# EPU.net
KiCad netlist of a schematic drawn in Altium Designer
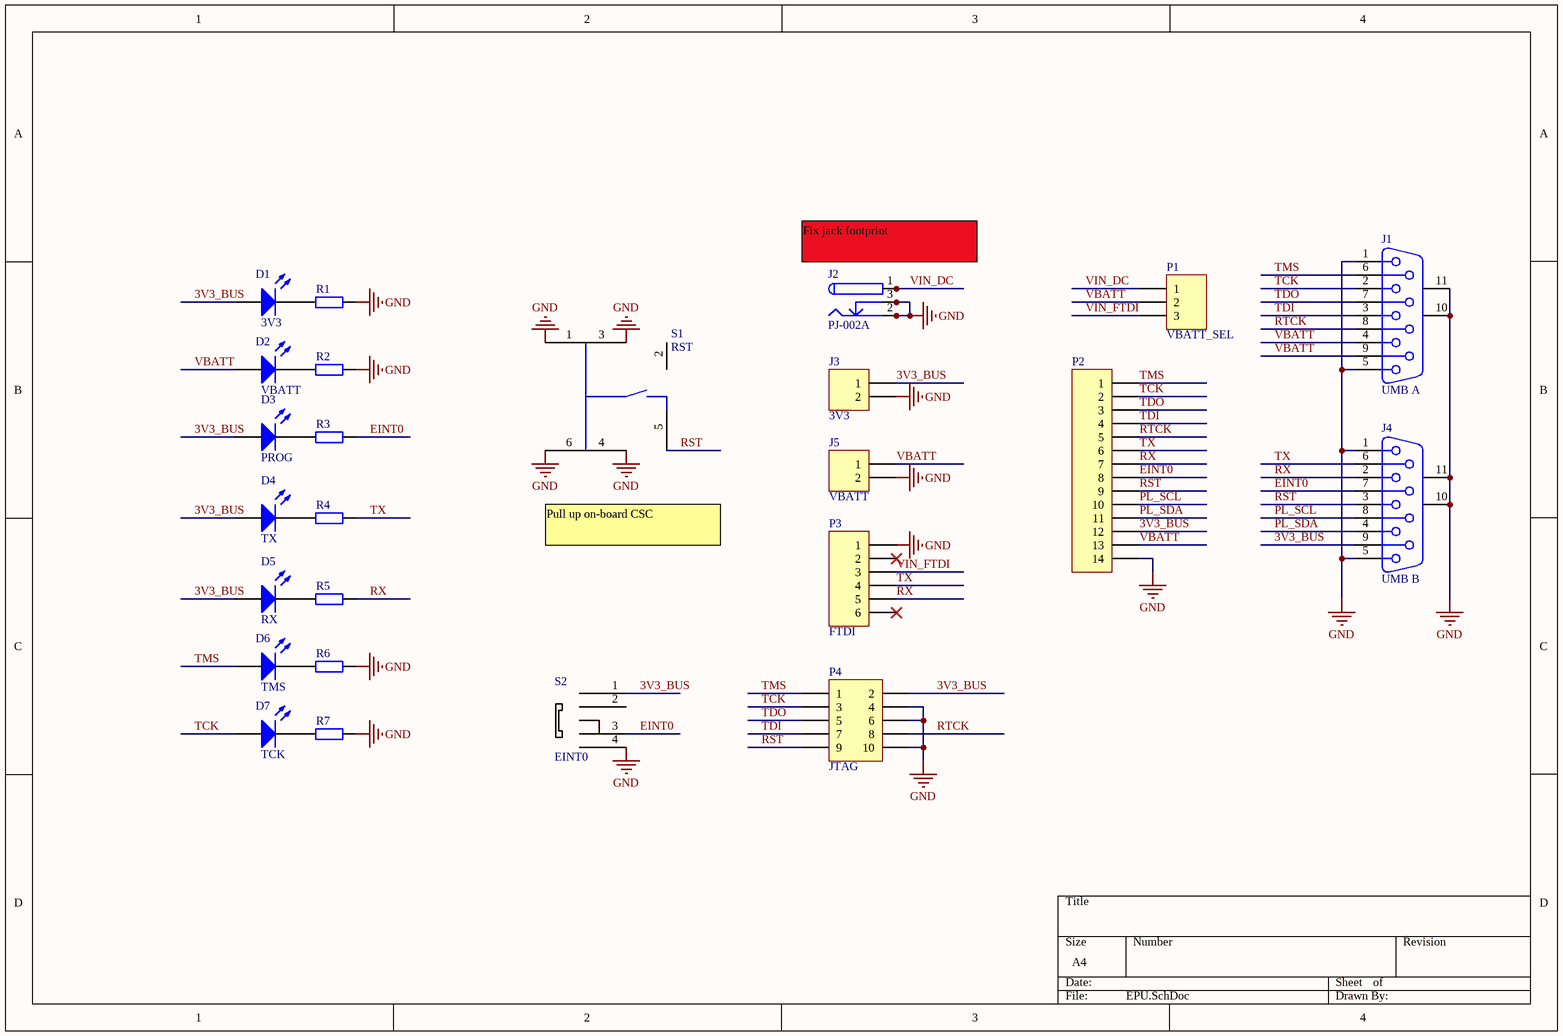
[diagram p0: EPU.SchDoc]

(export (version "E")
  (design (tool "Eeschema 10.0.6"))
  (components
    (comp (ref "D1")
      (value "3V3")
      (footprint "ASMT-Rx45")
      (description "Typical INFRARED GaAs LED 0603")
      (fields (field (name "PUBLISHER") "Altium Limited"))
      (libsource (lib "CSC") (part "LED"))
    )
    (comp (ref "D2")
      (value "VBATT")
      (footprint "ASMT-Rx45")
      (description "Typical INFRARED GaAs LED 0603")
      (fields (field (name "PUBLISHER") "Altium Limited"))
      (libsource (lib "CSC") (part "LED"))
    )
    (comp (ref "D3")
      (value "PROG")
      (footprint "ASMT-Rx45")
      (description "Typical INFRARED GaAs LED 0603")
      (fields (field (name "PUBLISHER") "Altium Limited"))
      (libsource (lib "CSC") (part "LED"))
    )
    (comp (ref "D4")
      (value "TX")
      (footprint "ASMT-Rx45")
      (description "Typical INFRARED GaAs LED 0603")
      (fields (field (name "PUBLISHER") "Altium Limited"))
      (libsource (lib "CSC") (part "LED"))
    )
    (comp (ref "D5")
      (value "RX")
      (footprint "ASMT-Rx45")
      (description "Typical INFRARED GaAs LED 0603")
      (fields (field (name "PUBLISHER") "Altium Limited"))
      (libsource (lib "CSC") (part "LED"))
    )
    (comp (ref "D6")
      (value "TMS")
      (footprint "ASMT-Rx45")
      (description "Typical INFRARED GaAs LED 0603")
      (fields (field (name "PUBLISHER") "Altium Limited"))
      (libsource (lib "CSC") (part "LED"))
    )
    (comp (ref "D7")
      (value "TCK")
      (footprint "ASMT-Rx45")
      (description "Typical INFRARED GaAs LED 0603")
      (fields (field (name "PUBLISHER") "Altium Limited"))
      (libsource (lib "CSC") (part "LED"))
    )
    (comp (ref "J1")
      (value "UMB A")
      (footprint "DSUB1.385-2H9")
      (description "Receptacle Assembly, 9 Position, Right Angle")
      (fields (field (name "PUBLISHER") "Altium Limited"))
      (libsource (lib "Miscellaneous Connectors") (part "D Connector 9"))
    )
    (comp (ref "J2")
      (value "PJ-002A")
      (footprint "PJ-002A")
      (description "Low Voltage Power Supply Connector")
      (fields (field (name "PUBLISHER") "Altium Limited"))
      (libsource (lib "Miscellaneous Connectors") (part "PWR2.5"))
    )
    (comp (ref "J3")
      (value "3V3")
      (footprint "5.05mm Terminal Block")
      (description "Header, 2-Pin")
      (fields (field (name "PUBLISHER") "Altium Limited"))
      (libsource (lib "Miscellaneous Connectors") (part "Header 2"))
    )
    (comp (ref "J4")
      (value "UMB B")
      (footprint "DSUB1.385-2H9")
      (description "Receptacle Assembly, 9 Position, Right Angle")
      (fields (field (name "PUBLISHER") "Altium Limited"))
      (libsource (lib "Miscellaneous Connectors") (part "D Connector 9"))
    )
    (comp (ref "J5")
      (value "VBATT")
      (footprint "5.05mm Terminal Block")
      (description "Header, 2-Pin")
      (fields (field (name "PUBLISHER") "Altium Limited"))
      (libsource (lib "Miscellaneous Connectors") (part "Header 2"))
    )
    (comp (ref "P1")
      (value "VBATT_SEL")
      (footprint "HDR1X3")
      (description "Header, 3-Pin")
      (fields (field (name "PUBLISHER") "Altium Limited"))
      (libsource (lib "Miscellaneous Connectors") (part "Header 3"))
    )
    (comp (ref "P2")
      (value "~")
      (footprint "HDR1X14")
      (description "Header, 14-Pin")
      (fields (field (name "PUBLISHER") "Altium Limited"))
      (libsource (lib "Miscellaneous Connectors") (part "Header 14"))
    )
    (comp (ref "P3")
      (value "FTDI")
      (footprint "HDR1X6")
      (description "Header, 6-Pin")
      (fields (field (name "PUBLISHER") "Altium Limited"))
      (libsource (lib "Miscellaneous Connectors") (part "Header 6"))
    )
    (comp (ref "P4")
      (value "JTAG")
      (footprint "FTSH-105-01-L-DV-TR")
      (description "Header, 5-Pin, Dual row")
      (fields (field (name "PUBLISHER") "Altium Limited"))
      (libsource (lib "Miscellaneous Connectors") (part "Header 5X2"))
    )
    (comp (ref "R1")
      (value "Res3")
      (footprint "0805 Cap")
      (description "Resistor")
      (fields (field (name "PUBLISHER") "Altium Limited"))
      (libsource (lib "CSC") (part "Res3"))
    )
    (comp (ref "R2")
      (value "Res3")
      (footprint "0805 Cap")
      (description "Resistor")
      (fields (field (name "PUBLISHER") "Altium Limited"))
      (libsource (lib "CSC") (part "Res3"))
    )
    (comp (ref "R3")
      (value "Res3")
      (footprint "0805 Cap")
      (description "Resistor")
      (fields (field (name "PUBLISHER") "Altium Limited"))
      (libsource (lib "CSC") (part "Res3"))
    )
    (comp (ref "R4")
      (value "Res3")
      (footprint "0805 Cap")
      (description "Resistor")
      (fields (field (name "PUBLISHER") "Altium Limited"))
      (libsource (lib "CSC") (part "Res3"))
    )
    (comp (ref "R5")
      (value "Res3")
      (footprint "0805 Cap")
      (description "Resistor")
      (fields (field (name "PUBLISHER") "Altium Limited"))
      (libsource (lib "CSC") (part "Res3"))
    )
    (comp (ref "R6")
      (value "Res3")
      (footprint "0805 Cap")
      (description "Resistor")
      (fields (field (name "PUBLISHER") "Altium Limited"))
      (libsource (lib "CSC") (part "Res3"))
    )
    (comp (ref "R7")
      (value "Res3")
      (footprint "0805 Cap")
      (description "Resistor")
      (fields (field (name "PUBLISHER") "Altium Limited"))
      (libsource (lib "CSC") (part "Res3"))
    )
    (comp (ref "S1")
      (value "RST")
      (footprint "K5A2")
      (description "Tact Switch")
      (libsource (lib "CSC") (part "KS2A"))
    )
    (comp (ref "S2")
      (value "EINT0")
      (footprint "MILL1300S")
      (description "Slide switch SP3T switch")
      (libsource (lib "CSC") (part "MLL1300S"))
    )
  )
  (nets
    (net (code "1") (name "/3V3_BUS") (class "Default")
      (node (ref "D1") (pin "1") (pinfunction "A_1") (pintype "passive"))
      (node (ref "D3") (pin "1") (pinfunction "A_1") (pintype "passive"))
      (node (ref "D4") (pin "1") (pinfunction "A_1") (pintype "passive"))
      (node (ref "D5") (pin "1") (pinfunction "A_1") (pintype "passive"))
      (node (ref "J3") (pin "1") (pinfunction "1_1") (pintype "passive"))
      (node (ref "J4") (pin "9") (pinfunction "9_9") (pintype "passive"))
      (node (ref "P2") (pin "12") (pinfunction "12_12") (pintype "passive"))
      (node (ref "P4") (pin "2") (pinfunction "2_2") (pintype "passive"))
      (node (ref "S2") (pin "1") (pinfunction "1_1") (pintype "passive"))
    )
    (net (code "2") (name "/EINT0") (class "Default")
      (node (ref "J4") (pin "7") (pinfunction "7_7") (pintype "passive"))
      (node (ref "P2") (pin "8") (pinfunction "8_8") (pintype "passive"))
      (node (ref "R3") (pin "2") (pinfunction "2_2") (pintype "passive"))
      (node (ref "S2") (pin "3") (pinfunction "3_3") (pintype "passive"))
    )
    (net (code "3") (name "/PL_SCL") (class "Default")
      (node (ref "J4") (pin "8") (pinfunction "8_8") (pintype "passive"))
      (node (ref "P2") (pin "10") (pinfunction "10_10") (pintype "passive"))
    )
    (net (code "4") (name "/PL_SDA") (class "Default")
      (node (ref "J4") (pin "4") (pinfunction "4_4") (pintype "passive"))
      (node (ref "P2") (pin "11") (pinfunction "11_11") (pintype "passive"))
    )
    (net (code "5") (name "/RST") (class "Default")
      (node (ref "J4") (pin "3") (pinfunction "3_3") (pintype "passive"))
      (node (ref "P2") (pin "9") (pinfunction "9_9") (pintype "passive"))
      (node (ref "P4") (pin "9") (pinfunction "9_9") (pintype "passive"))
      (node (ref "S1") (pin "5") (pinfunction "5_5") (pintype "passive"))
    )
    (net (code "6") (name "/RTCK") (class "Default")
      (node (ref "J1") (pin "8") (pinfunction "8_8") (pintype "passive"))
      (node (ref "P2") (pin "5") (pinfunction "5_5") (pintype "passive"))
      (node (ref "P4") (pin "8") (pinfunction "8_8") (pintype "passive"))
    )
    (net (code "7") (name "/RX") (class "Default")
      (node (ref "J4") (pin "2") (pinfunction "2_2") (pintype "passive"))
      (node (ref "P2") (pin "7") (pinfunction "7_7") (pintype "passive"))
      (node (ref "P3") (pin "5") (pinfunction "5_5") (pintype "passive"))
      (node (ref "R5") (pin "2") (pinfunction "2_2") (pintype "passive"))
    )
    (net (code "8") (name "/TCK") (class "Default")
      (node (ref "D7") (pin "1") (pinfunction "A_1") (pintype "passive"))
      (node (ref "J1") (pin "2") (pinfunction "2_2") (pintype "passive"))
      (node (ref "P2") (pin "2") (pinfunction "2_2") (pintype "passive"))
      (node (ref "P4") (pin "3") (pinfunction "3_3") (pintype "passive"))
    )
    (net (code "9") (name "/TDI") (class "Default")
      (node (ref "J1") (pin "3") (pinfunction "3_3") (pintype "passive"))
      (node (ref "P2") (pin "4") (pinfunction "4_4") (pintype "passive"))
      (node (ref "P4") (pin "7") (pinfunction "7_7") (pintype "passive"))
    )
    (net (code "10") (name "/TDO") (class "Default")
      (node (ref "J1") (pin "7") (pinfunction "7_7") (pintype "passive"))
      (node (ref "P2") (pin "3") (pinfunction "3_3") (pintype "passive"))
      (node (ref "P4") (pin "5") (pinfunction "5_5") (pintype "passive"))
    )
    (net (code "11") (name "/TMS") (class "Default")
      (node (ref "D6") (pin "1") (pinfunction "A_1") (pintype "passive"))
      (node (ref "J1") (pin "6") (pinfunction "6_6") (pintype "passive"))
      (node (ref "P2") (pin "1") (pinfunction "1_1") (pintype "passive"))
      (node (ref "P4") (pin "1") (pinfunction "1_1") (pintype "passive"))
    )
    (net (code "12") (name "/TX") (class "Default")
      (node (ref "J4") (pin "6") (pinfunction "6_6") (pintype "passive"))
      (node (ref "P2") (pin "6") (pinfunction "6_6") (pintype "passive"))
      (node (ref "P3") (pin "4") (pinfunction "4_4") (pintype "passive"))
      (node (ref "R4") (pin "2") (pinfunction "2_2") (pintype "passive"))
    )
    (net (code "13") (name "/VBATT") (class "Default")
      (node (ref "D2") (pin "1") (pinfunction "A_1") (pintype "passive"))
      (node (ref "J1") (pin "4") (pinfunction "4_4") (pintype "passive"))
      (node (ref "J1") (pin "9") (pinfunction "9_9") (pintype "passive"))
      (node (ref "J5") (pin "1") (pinfunction "1_1") (pintype "passive"))
      (node (ref "P1") (pin "2") (pinfunction "2_2") (pintype "passive"))
      (node (ref "P2") (pin "13") (pinfunction "13_13") (pintype "passive"))
    )
    (net (code "14") (name "/VIN_DC") (class "Default")
      (node (ref "J2") (pin "1") (pinfunction "1_1") (pintype "power_in"))
      (node (ref "J2") (pin "1A") (pinfunction "1A_1A") (pintype "power_in"))
      (node (ref "J2") (pin "1B") (pinfunction "1B_1B") (pintype "power_in"))
      (node (ref "P1") (pin "1") (pinfunction "1_1") (pintype "passive"))
    )
    (net (code "15") (name "/VIN_FTDI") (class "Default")
      (node (ref "P1") (pin "3") (pinfunction "3_3") (pintype "passive"))
      (node (ref "P3") (pin "3") (pinfunction "3_3") (pintype "passive"))
    )
    (net (code "16") (name "GND") (class "Default")
      (node (ref "J1") (pin "1") (pinfunction "1_1") (pintype "passive"))
      (node (ref "J1") (pin "10") (pinfunction "MH1_10") (pintype "passive"))
      (node (ref "J1") (pin "11") (pinfunction "MH2_11") (pintype "passive"))
      (node (ref "J1") (pin "5") (pinfunction "5_5") (pintype "passive"))
      (node (ref "J2") (pin "2") (pinfunction "2_2") (pintype "power_in"))
      (node (ref "J2") (pin "2A") (pinfunction "2A_2A") (pintype "power_in"))
      (node (ref "J2") (pin "2B") (pinfunction "2B_2B") (pintype "power_in"))
      (node (ref "J2") (pin "3") (pinfunction "3_3") (pintype "power_in"))
      (node (ref "J2") (pin "3A") (pinfunction "3A_3A") (pintype "power_in"))
      (node (ref "J2") (pin "3B") (pinfunction "3B_3B") (pintype "power_in"))
      (node (ref "J3") (pin "2") (pinfunction "2_2") (pintype "passive"))
      (node (ref "J4") (pin "1") (pinfunction "1_1") (pintype "passive"))
      (node (ref "J4") (pin "10") (pinfunction "MH1_10") (pintype "passive"))
      (node (ref "J4") (pin "11") (pinfunction "MH2_11") (pintype "passive"))
      (node (ref "J4") (pin "5") (pinfunction "5_5") (pintype "passive"))
      (node (ref "J5") (pin "2") (pinfunction "2_2") (pintype "passive"))
      (node (ref "P2") (pin "14") (pinfunction "14_14") (pintype "passive"))
      (node (ref "P3") (pin "1") (pinfunction "1_1") (pintype "passive"))
      (node (ref "P4") (pin "10") (pinfunction "10_10") (pintype "passive"))
      (node (ref "P4") (pin "4") (pinfunction "4_4") (pintype "passive"))
      (node (ref "P4") (pin "6") (pinfunction "6_6") (pintype "passive"))
      (node (ref "R1") (pin "2") (pinfunction "2_2") (pintype "passive"))
      (node (ref "R2") (pin "2") (pinfunction "2_2") (pintype "passive"))
      (node (ref "R6") (pin "2") (pinfunction "2_2") (pintype "passive"))
      (node (ref "R7") (pin "2") (pinfunction "2_2") (pintype "passive"))
      (node (ref "S1") (pin "1") (pinfunction "1_1") (pintype "power_in"))
      (node (ref "S1") (pin "3") (pinfunction "3_3") (pintype "power_in"))
      (node (ref "S1") (pin "4") (pinfunction "4_4") (pintype "power_in"))
      (node (ref "S1") (pin "6") (pinfunction "6_6") (pintype "power_in"))
      (node (ref "S2") (pin "4") (pinfunction "4_4") (pintype "passive"))
    )
    (net (code "17") (name "Net-(D1-K)") (class "Default")
      (node (ref "D1") (pin "2") (pinfunction "K_2") (pintype "passive"))
      (node (ref "R1") (pin "1") (pinfunction "1_1") (pintype "passive"))
    )
    (net (code "18") (name "Net-(D2-K)") (class "Default")
      (node (ref "D2") (pin "2") (pinfunction "K_2") (pintype "passive"))
      (node (ref "R2") (pin "1") (pinfunction "1_1") (pintype "passive"))
    )
    (net (code "19") (name "Net-(D3-K)") (class "Default")
      (node (ref "D3") (pin "2") (pinfunction "K_2") (pintype "passive"))
      (node (ref "R3") (pin "1") (pinfunction "1_1") (pintype "passive"))
    )
    (net (code "20") (name "Net-(D4-K)") (class "Default")
      (node (ref "D4") (pin "2") (pinfunction "K_2") (pintype "passive"))
      (node (ref "R4") (pin "1") (pinfunction "1_1") (pintype "passive"))
    )
    (net (code "21") (name "Net-(D5-K)") (class "Default")
      (node (ref "D5") (pin "2") (pinfunction "K_2") (pintype "passive"))
      (node (ref "R5") (pin "1") (pinfunction "1_1") (pintype "passive"))
    )
    (net (code "22") (name "Net-(D6-K)") (class "Default")
      (node (ref "D6") (pin "2") (pinfunction "K_2") (pintype "passive"))
      (node (ref "R6") (pin "1") (pinfunction "1_1") (pintype "passive"))
    )
    (net (code "23") (name "Net-(D7-K)") (class "Default")
      (node (ref "D7") (pin "2") (pinfunction "K_2") (pintype "passive"))
      (node (ref "R7") (pin "1") (pinfunction "1_1") (pintype "passive"))
    )
    (net (code "24") (name "unconnected-(P3-Pad2)") (class "Default")
      (node (ref "P3") (pin "2") (pinfunction "2_2") (pintype "passive+no_connect"))
    )
    (net (code "25") (name "unconnected-(P3-Pad6)") (class "Default")
      (node (ref "P3") (pin "6") (pinfunction "6_6") (pintype "passive+no_connect"))
    )
    (net (code "26") (name "unconnected-(S1-Pad2)") (class "Default")
      (node (ref "S1") (pin "2") (pinfunction "2_2") (pintype "power_in"))
    )
    (net (code "27") (name "unconnected-(S2-Pad2)") (class "Default")
      (node (ref "S2") (pin "2") (pinfunction "2_2") (pintype "passive"))
    )
  )
)
